# SCH_keyboard_2024-07-08.net
KiCad netlist of a schematic drawn in EasyEDA
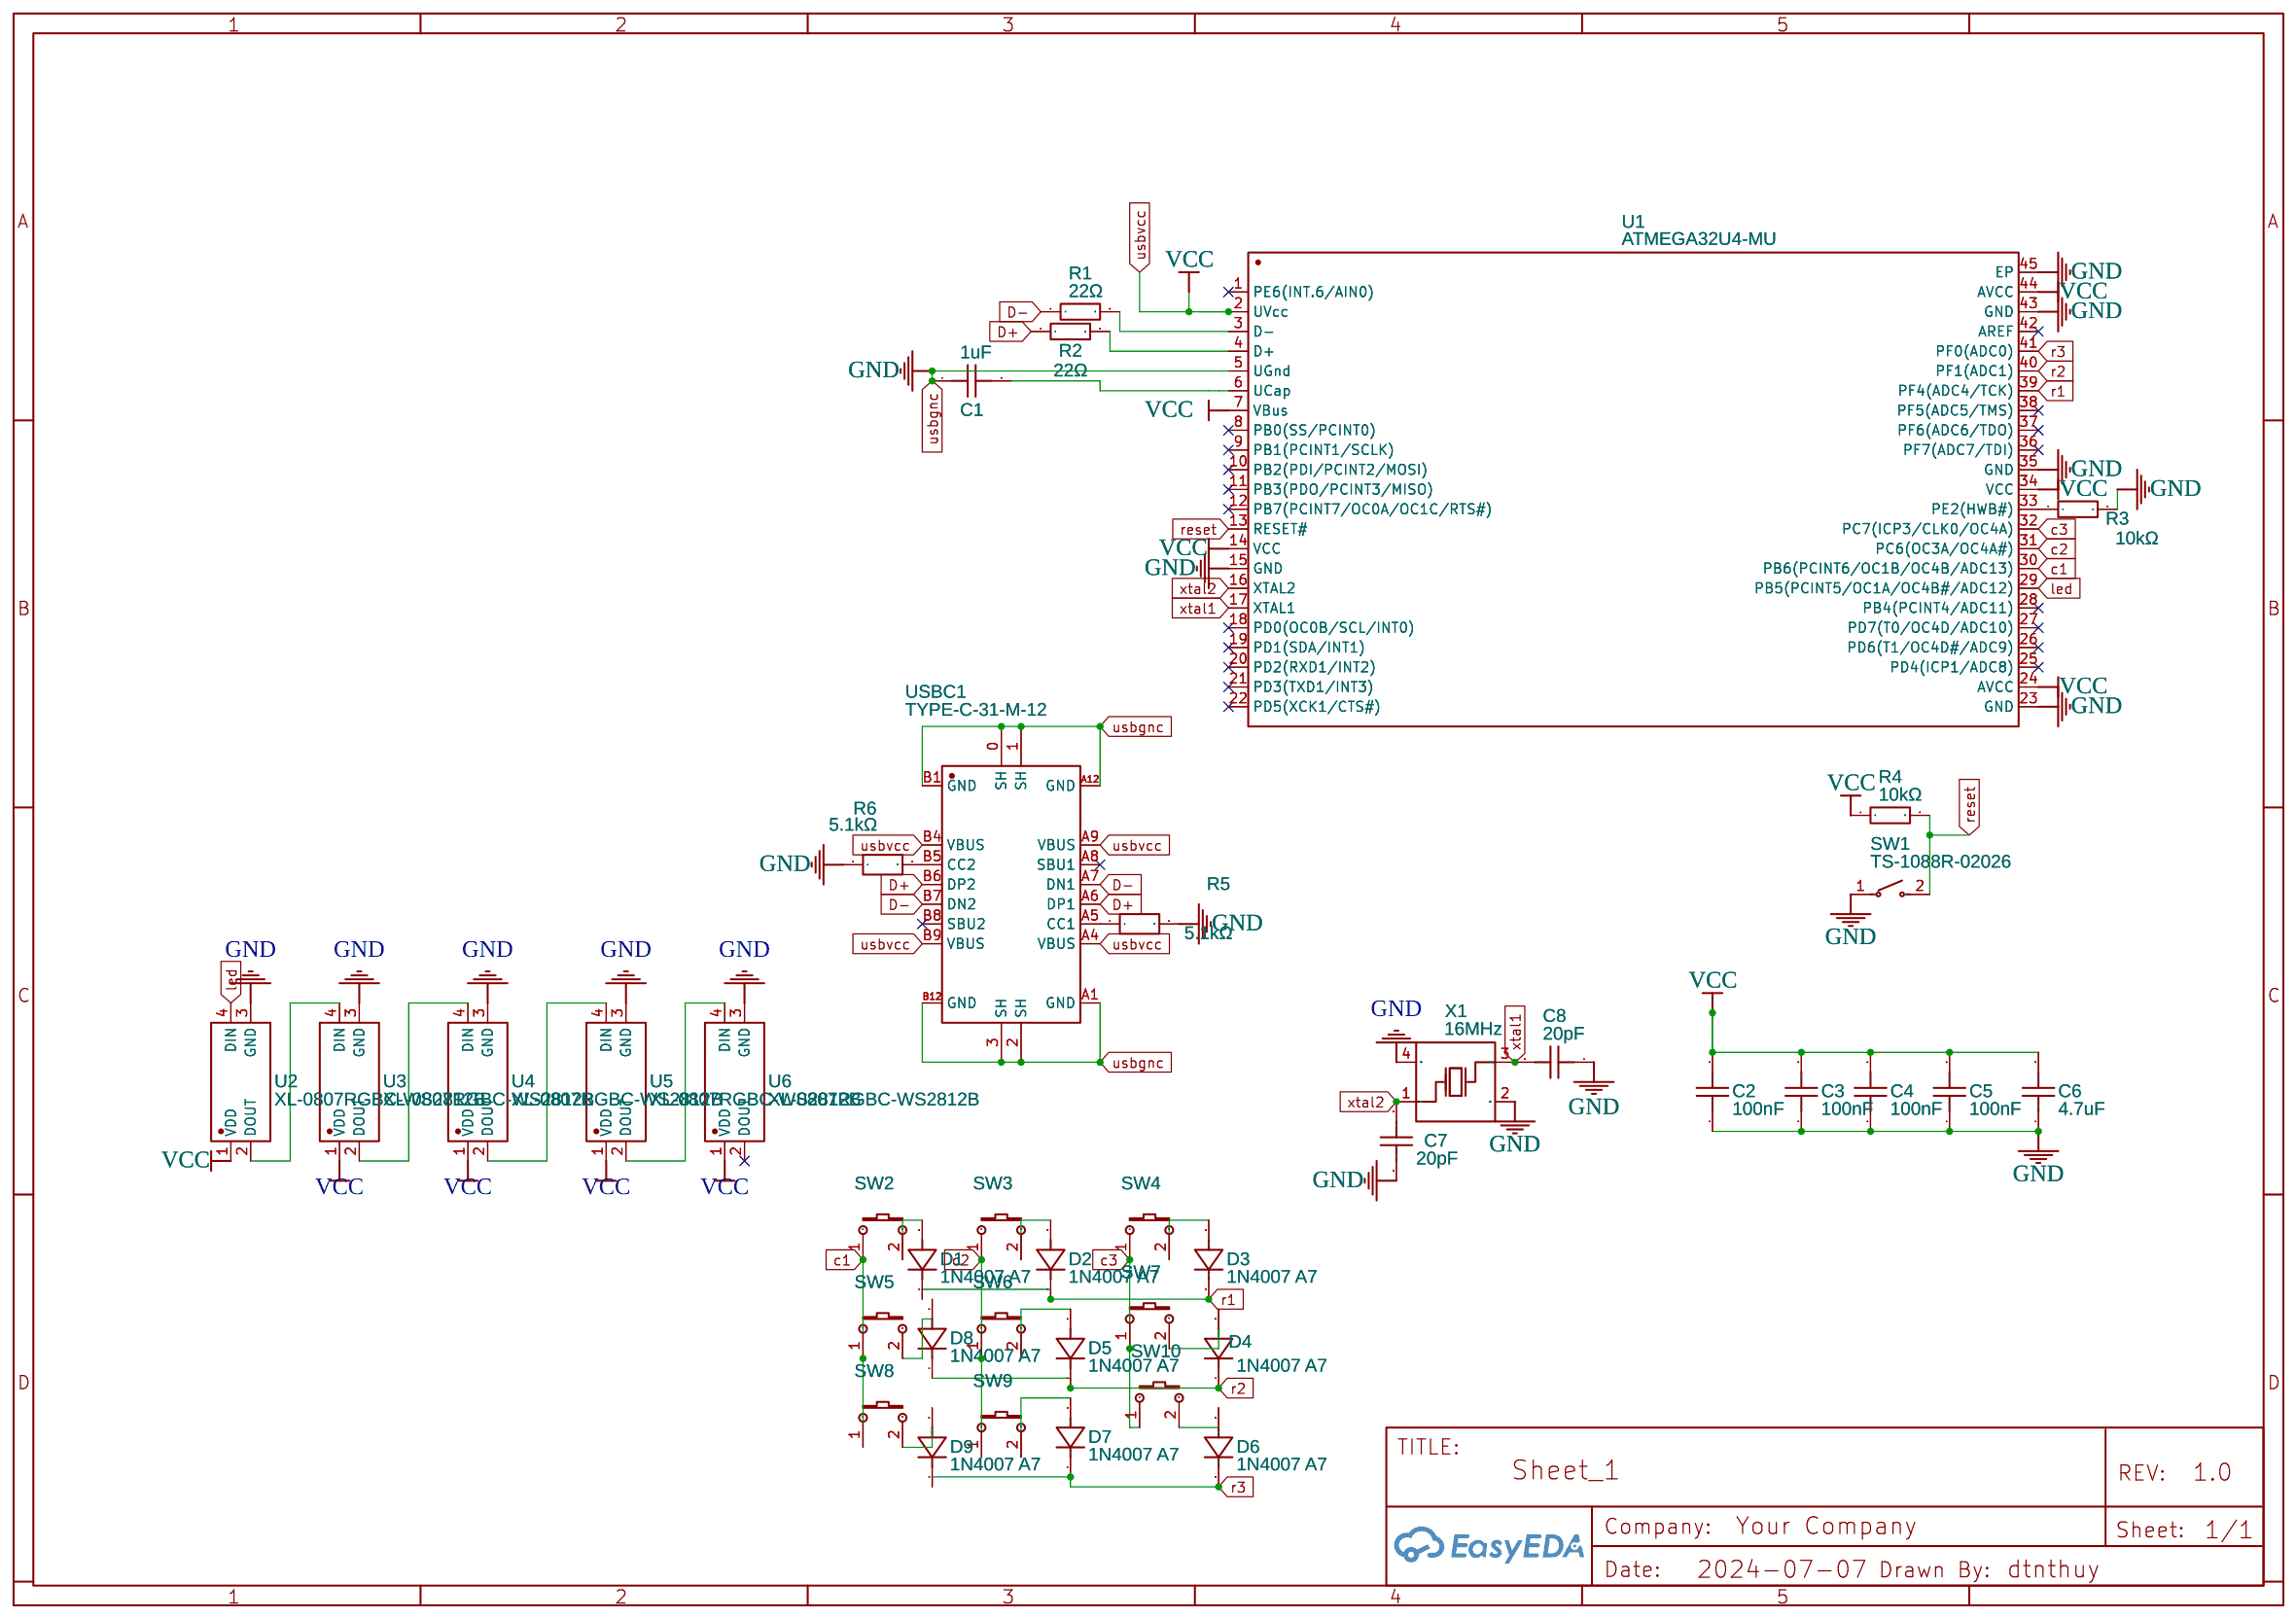
[diagram p0: schematic sheet]

(export (version "E")
  (design (tool "Eeschema 10.0.6"))
  (components
    (comp (ref "C1")
      (value "1uF")
      (fields
        (field (name "Manufacturer Part") "CS1608X7R105K250NRB")
        (field (name "Manufacturer") "SAMWHA(三和)")
      )
      (libsource (lib "") (part "CS1608X7R105K250NRB"))
    )
    (comp (ref "C2")
      (value "100nF")
      (fields
        (field (name "Manufacturer Part") "C0402X7R104K250NT")
        (field (name "Manufacturer") "SANYEAR(叁叶源)")
      )
      (libsource (lib "") (part "C0402X7R104K250NT"))
    )
    (comp (ref "C3")
      (value "100nF")
      (fields
        (field (name "Manufacturer Part") "C0402X7R104K250NT")
        (field (name "Manufacturer") "SANYEAR(叁叶源)")
      )
      (libsource (lib "") (part "C0402X7R104K250NT"))
    )
    (comp (ref "C4")
      (value "100nF")
      (fields
        (field (name "Manufacturer Part") "C0402X7R104K250NT")
        (field (name "Manufacturer") "SANYEAR(叁叶源)")
      )
      (libsource (lib "") (part "C0402X7R104K250NT"))
    )
    (comp (ref "C5")
      (value "100nF")
      (fields
        (field (name "Manufacturer Part") "C0402X7R104K250NT")
        (field (name "Manufacturer") "SANYEAR(叁叶源)")
      )
      (libsource (lib "") (part "C0402X7R104K250NT"))
    )
    (comp (ref "C6")
      (value "4.7uF")
      (fields (field (name "Manufacturer Part") "C1005X6S0G475MTJ00E") (field (name "Manufacturer") "TDK"))
      (libsource (lib "") (part "C1005X6S0G475MTJ00E"))
    )
    (comp (ref "C7")
      (value "20pF")
      (fields (field (name "Manufacturer Part") "0201CG200K500NT") (field (name "Manufacturer") "FH(风华)"))
      (libsource (lib "") (part "0201CG200K500NT"))
    )
    (comp (ref "C8")
      (value "20pF")
      (fields (field (name "Manufacturer Part") "0201CG200K500NT") (field (name "Manufacturer") "FH(风华)"))
      (libsource (lib "") (part "0201CG200K500NT_1"))
    )
    (comp (ref "D1")
      (value "1N4007 A7")
      (fields (field (name "Manufacturer") "MSKSEMI(美森科)"))
      (libsource (lib "") (part "1N4007 A7"))
    )
    (comp (ref "D2")
      (value "1N4007 A7")
      (fields (field (name "Manufacturer") "MSKSEMI(美森科)"))
      (libsource (lib "") (part "1N4007 A7"))
    )
    (comp (ref "D3")
      (value "1N4007 A7")
      (fields (field (name "Manufacturer") "MSKSEMI(美森科)"))
      (libsource (lib "") (part "1N4007 A7"))
    )
    (comp (ref "D4")
      (value "1N4007 A7")
      (fields (field (name "Manufacturer") "MSKSEMI(美森科)"))
      (libsource (lib "") (part "1N4007 A7"))
    )
    (comp (ref "D5")
      (value "1N4007 A7")
      (fields (field (name "Manufacturer") "MSKSEMI(美森科)"))
      (libsource (lib "") (part "1N4007 A7"))
    )
    (comp (ref "D6")
      (value "1N4007 A7")
      (fields (field (name "Manufacturer") "MSKSEMI(美森科)"))
      (libsource (lib "") (part "1N4007 A7"))
    )
    (comp (ref "D7")
      (value "1N4007 A7")
      (fields (field (name "Manufacturer") "MSKSEMI(美森科)"))
      (libsource (lib "") (part "1N4007 A7"))
    )
    (comp (ref "D8")
      (value "1N4007 A7")
      (fields (field (name "Manufacturer") "MSKSEMI(美森科)"))
      (libsource (lib "") (part "1N4007 A7"))
    )
    (comp (ref "D9")
      (value "1N4007 A7")
      (fields (field (name "Manufacturer") "MSKSEMI(美森科)"))
      (libsource (lib "") (part "1N4007 A7"))
    )
    (comp (ref "R1")
      (value "22Ω")
      (fields
        (field (name "Manufacturer Part") "0603WAJ0220T5E")
        (field (name "Manufacturer") "UNI-ROYAL(厚声)")
      )
      (libsource (lib "") (part "0603WAJ0220T5E"))
    )
    (comp (ref "R2")
      (value "22Ω")
      (fields
        (field (name "Manufacturer Part") "0603WAJ0220T5E")
        (field (name "Manufacturer") "UNI-ROYAL(厚声)")
      )
      (libsource (lib "") (part "0603WAJ0220T5E"))
    )
    (comp (ref "R3")
      (value "10kΩ")
      (fields
        (field (name "Manufacturer Part") "0805W8F1002T5E")
        (field (name "Manufacturer") "UNI-ROYAL(厚声)")
      )
      (libsource (lib "") (part "0805W8F1002T5E"))
    )
    (comp (ref "R4")
      (value "10kΩ")
      (fields
        (field (name "Manufacturer Part") "0805W8F1002T5E")
        (field (name "Manufacturer") "UNI-ROYAL(厚声)")
      )
      (libsource (lib "") (part "0805W8F1002T5E"))
    )
    (comp (ref "R5")
      (value "5.1kΩ")
      (fields (field (name "Manufacturer Part") "RK73H1JTTD5101D") (field (name "Manufacturer") "KOA"))
      (libsource (lib "") (part "RK73H1JTTD5101D"))
    )
    (comp (ref "R6")
      (value "5.1kΩ")
      (fields (field (name "Manufacturer Part") "RK73H1JTTD5101D") (field (name "Manufacturer") "KOA"))
      (libsource (lib "") (part "RK73H1JTTD5101D"))
    )
    (comp (ref "SW1")
      (value "TS-1088R-02026")
      (fields (field (name "Manufacturer") "XUNPU(讯普)"))
      (libsource (lib "") (part "TS-1088R-02026"))
    )
    (comp (ref "SW2")
      (value "MX1A-11NW")
      (fields (field (name "Manufacturer") "CHERRY"))
      (libsource (lib "") (part "MX1A-11NW"))
    )
    (comp (ref "SW3")
      (value "MX1A-11NW")
      (fields (field (name "Manufacturer") "CHERRY"))
      (libsource (lib "") (part "MX1A-11NW"))
    )
    (comp (ref "SW4")
      (value "MX1A-11NW")
      (fields (field (name "Manufacturer") "CHERRY"))
      (libsource (lib "") (part "MX1A-11NW"))
    )
    (comp (ref "SW5")
      (value "MX1A-11NW")
      (fields (field (name "Manufacturer") "CHERRY"))
      (libsource (lib "") (part "MX1A-11NW"))
    )
    (comp (ref "SW6")
      (value "MX1A-11NW")
      (fields (field (name "Manufacturer") "CHERRY"))
      (libsource (lib "") (part "MX1A-11NW"))
    )
    (comp (ref "SW7")
      (value "MX1A-11NW")
      (fields (field (name "Manufacturer") "CHERRY"))
      (libsource (lib "") (part "MX1A-11NW"))
    )
    (comp (ref "SW8")
      (value "MX1A-11NW")
      (fields (field (name "Manufacturer") "CHERRY"))
      (libsource (lib "") (part "MX1A-11NW"))
    )
    (comp (ref "SW9")
      (value "MX1A-11NW")
      (fields (field (name "Manufacturer") "CHERRY"))
      (libsource (lib "") (part "MX1A-11NW"))
    )
    (comp (ref "SW10")
      (value "MX1A-11NW")
      (fields (field (name "Manufacturer") "CHERRY"))
      (libsource (lib "") (part "MX1A-11NW"))
    )
    (comp (ref "U1")
      (value "ATMEGA32U4-MU")
      (fields (field (name "Manufacturer") "MICROCHIP(美国微芯)"))
      (libsource (lib "") (part "ATMEGA32U4-MU"))
    )
    (comp (ref "U2")
      (value "XL-0807RGBC-WS2812B")
      (fields (field (name "Manufacturer") "XINGLIGHT(成兴光)"))
      (libsource (lib "") (part "XL-0807RGBC-WS2812B"))
    )
    (comp (ref "U3")
      (value "XL-0807RGBC-WS2812B")
      (fields (field (name "Manufacturer") "XINGLIGHT(成兴光)"))
      (libsource (lib "") (part "XL-0807RGBC-WS2812B"))
    )
    (comp (ref "U4")
      (value "XL-0807RGBC-WS2812B")
      (fields (field (name "Manufacturer") "XINGLIGHT(成兴光)"))
      (libsource (lib "") (part "XL-0807RGBC-WS2812B"))
    )
    (comp (ref "U5")
      (value "XL-0807RGBC-WS2812B")
      (fields (field (name "Manufacturer") "XINGLIGHT(成兴光)"))
      (libsource (lib "") (part "XL-0807RGBC-WS2812B"))
    )
    (comp (ref "U6")
      (value "XL-0807RGBC-WS2812B")
      (fields (field (name "Manufacturer") "XINGLIGHT(成兴光)"))
      (libsource (lib "") (part "XL-0807RGBC-WS2812B"))
    )
    (comp (ref "USBC1")
      (value "TYPE-C-31-M-12")
      (fields (field (name "Manufacturer") "韩国韩荣"))
      (libsource (lib "") (part "TYPE-C-31-M-12"))
    )
    (comp (ref "X1")
      (value "16MHz")
      (fields (field (name "Manufacturer Part") "X322516MOB4SI") (field (name "Manufacturer") "YXC(扬兴晶振)"))
      (libsource (lib "") (part "X322516MOB4SI"))
    )
  )
  (nets
    (net (code "1") (name "D+") (class "Default")
      (node (ref "R2") (pin "1") (pinfunction "1_1") (pintype "input"))
      (node (ref "USBC1") (pin "A6") (pinfunction "DP1_A6") (pintype "unspecified"))
      (node (ref "USBC1") (pin "B6") (pinfunction "DP2_B6") (pintype "unspecified"))
    )
    (net (code "2") (name "D-") (class "Default")
      (node (ref "R1") (pin "1") (pinfunction "1_1") (pintype "input"))
      (node (ref "USBC1") (pin "A7") (pinfunction "DN1_A7") (pintype "unspecified"))
      (node (ref "USBC1") (pin "B7") (pinfunction "DN2_B7") (pintype "unspecified"))
    )
    (net (code "3") (name "Net-(D1-A)") (class "Default")
      (node (ref "D1") (pin "2") (pinfunction "A_2") (pintype "unspecified"))
      (node (ref "SW2") (pin "2") (pinfunction "2_2") (pintype "unspecified"))
    )
    (net (code "4") (name "Net-(D2-A)") (class "Default")
      (node (ref "D2") (pin "2") (pinfunction "A_2") (pintype "unspecified"))
      (node (ref "SW3") (pin "2") (pinfunction "2_2") (pintype "unspecified"))
    )
    (net (code "5") (name "Net-(D3-A)") (class "Default")
      (node (ref "D3") (pin "2") (pinfunction "A_2") (pintype "unspecified"))
      (node (ref "SW4") (pin "2") (pinfunction "2_2") (pintype "unspecified"))
    )
    (net (code "6") (name "Net-(D4-A)") (class "Default")
      (node (ref "D4") (pin "2") (pinfunction "A_2") (pintype "unspecified"))
      (node (ref "SW7") (pin "2") (pinfunction "2_2") (pintype "unspecified"))
    )
    (net (code "7") (name "Net-(D5-A)") (class "Default")
      (node (ref "D5") (pin "2") (pinfunction "A_2") (pintype "unspecified"))
      (node (ref "SW6") (pin "2") (pinfunction "2_2") (pintype "unspecified"))
    )
    (net (code "8") (name "Net-(D6-A)") (class "Default")
      (node (ref "D6") (pin "2") (pinfunction "A_2") (pintype "unspecified"))
      (node (ref "SW10") (pin "2") (pinfunction "2_2") (pintype "unspecified"))
    )
    (net (code "9") (name "Net-(D7-A)") (class "Default")
      (node (ref "D7") (pin "2") (pinfunction "A_2") (pintype "unspecified"))
      (node (ref "SW9") (pin "2") (pinfunction "2_2") (pintype "unspecified"))
    )
    (net (code "10") (name "Net-(D8-A)") (class "Default")
      (node (ref "D8") (pin "2") (pinfunction "A_2") (pintype "unspecified"))
      (node (ref "SW5") (pin "2") (pinfunction "2_2") (pintype "unspecified"))
    )
    (net (code "11") (name "Net-(D9-A)") (class "Default")
      (node (ref "D9") (pin "2") (pinfunction "A_2") (pintype "unspecified"))
      (node (ref "SW8") (pin "2") (pinfunction "2_2") (pintype "unspecified"))
    )
    (net (code "12") (name "Net-(U1-D+)") (class "Default")
      (node (ref "R2") (pin "2") (pinfunction "2_2") (pintype "input"))
      (node (ref "U1") (pin "4") (pinfunction "D+_4") (pintype "unspecified"))
    )
    (net (code "13") (name "Net-(U1-D-)") (class "Default")
      (node (ref "R1") (pin "2") (pinfunction "2_2") (pintype "input"))
      (node (ref "U1") (pin "3") (pinfunction "D-_3") (pintype "unspecified"))
    )
    (net (code "14") (name "Net-(U1-PE2(HWB#))") (class "Default")
      (node (ref "R3") (pin "1") (pinfunction "1_1") (pintype "input"))
      (node (ref "U1") (pin "33") (pinfunction "PE2(HWB#)_33") (pintype "unspecified"))
    )
    (net (code "15") (name "Net-(U1-UCap)") (class "Default")
      (node (ref "C1") (pin "2") (pinfunction "2_2") (pintype "unspecified"))
      (node (ref "U1") (pin "6") (pinfunction "UCap_6") (pintype "unspecified"))
    )
    (net (code "16") (name "Net-(U2-DOUT)") (class "Default")
      (node (ref "U2") (pin "2") (pinfunction "DOUT_2") (pintype "unspecified"))
      (node (ref "U3") (pin "4") (pinfunction "DIN_4") (pintype "unspecified"))
    )
    (net (code "17") (name "Net-(U3-DOUT)") (class "Default")
      (node (ref "U3") (pin "2") (pinfunction "DOUT_2") (pintype "unspecified"))
      (node (ref "U4") (pin "4") (pinfunction "DIN_4") (pintype "unspecified"))
    )
    (net (code "18") (name "Net-(U4-DOUT)") (class "Default")
      (node (ref "U4") (pin "2") (pinfunction "DOUT_2") (pintype "unspecified"))
      (node (ref "U5") (pin "4") (pinfunction "DIN_4") (pintype "unspecified"))
    )
    (net (code "19") (name "Net-(U5-DOUT)") (class "Default")
      (node (ref "U5") (pin "2") (pinfunction "DOUT_2") (pintype "unspecified"))
      (node (ref "U6") (pin "4") (pinfunction "DIN_4") (pintype "unspecified"))
    )
    (net (code "20") (name "Net-(USBC1-CC1)") (class "Default")
      (node (ref "R5") (pin "1") (pinfunction "1_1") (pintype "unspecified"))
      (node (ref "USBC1") (pin "A5") (pinfunction "CC1_A5") (pintype "unspecified"))
    )
    (net (code "21") (name "Net-(USBC1-CC2)") (class "Default")
      (node (ref "R6") (pin "2") (pinfunction "2_2") (pintype "unspecified"))
      (node (ref "USBC1") (pin "B5") (pinfunction "CC2_B5") (pintype "unspecified"))
    )
    (net (code "22") (name "c1") (class "Default")
      (node (ref "SW2") (pin "1") (pinfunction "1_1") (pintype "unspecified"))
      (node (ref "SW5") (pin "1") (pinfunction "1_1") (pintype "unspecified"))
      (node (ref "SW8") (pin "1") (pinfunction "1_1") (pintype "unspecified"))
      (node (ref "U1") (pin "30") (pinfunction "PB6(PCINT6/OC1B/OC4B/ADC13)_30") (pintype "unspecified"))
    )
    (net (code "23") (name "c2") (class "Default")
      (node (ref "SW3") (pin "1") (pinfunction "1_1") (pintype "unspecified"))
      (node (ref "SW6") (pin "1") (pinfunction "1_1") (pintype "unspecified"))
      (node (ref "SW9") (pin "1") (pinfunction "1_1") (pintype "unspecified"))
      (node (ref "U1") (pin "31") (pinfunction "PC6(OC3A/OC4A#)_31") (pintype "unspecified"))
    )
    (net (code "24") (name "c3") (class "Default")
      (node (ref "SW10") (pin "1") (pinfunction "1_1") (pintype "unspecified"))
      (node (ref "SW4") (pin "1") (pinfunction "1_1") (pintype "unspecified"))
      (node (ref "SW7") (pin "1") (pinfunction "1_1") (pintype "unspecified"))
      (node (ref "U1") (pin "32") (pinfunction "PC7(ICP3/CLK0/OC4A)_32") (pintype "unspecified"))
    )
    (net (code "25") (name "led") (class "Default")
      (node (ref "U1") (pin "29") (pinfunction "PB5(PCINT5/OC1A/OC4B#/ADC12)_29") (pintype "unspecified"))
      (node (ref "U2") (pin "4") (pinfunction "DIN_4") (pintype "unspecified"))
    )
    (net (code "26") (name "r1") (class "Default")
      (node (ref "D1") (pin "1") (pinfunction "K_1") (pintype "unspecified"))
      (node (ref "D2") (pin "1") (pinfunction "K_1") (pintype "unspecified"))
      (node (ref "D3") (pin "1") (pinfunction "K_1") (pintype "unspecified"))
      (node (ref "U1") (pin "39") (pinfunction "PF4(ADC4/TCK)_39") (pintype "unspecified"))
    )
    (net (code "27") (name "r2") (class "Default")
      (node (ref "D4") (pin "1") (pinfunction "K_1") (pintype "unspecified"))
      (node (ref "D5") (pin "1") (pinfunction "K_1") (pintype "unspecified"))
      (node (ref "D8") (pin "1") (pinfunction "K_1") (pintype "unspecified"))
      (node (ref "U1") (pin "40") (pinfunction "PF1(ADC1)_40") (pintype "unspecified"))
    )
    (net (code "28") (name "r3") (class "Default")
      (node (ref "D6") (pin "1") (pinfunction "K_1") (pintype "unspecified"))
      (node (ref "D7") (pin "1") (pinfunction "K_1") (pintype "unspecified"))
      (node (ref "D9") (pin "1") (pinfunction "K_1") (pintype "unspecified"))
      (node (ref "U1") (pin "41") (pinfunction "PF0(ADC0)_41") (pintype "unspecified"))
    )
    (net (code "29") (name "reset") (class "Default")
      (node (ref "R4") (pin "2") (pinfunction "2_2") (pintype "input"))
      (node (ref "SW1") (pin "2") (pinfunction "2_2") (pintype "unspecified"))
      (node (ref "U1") (pin "13") (pinfunction "RESET#_13") (pintype "unspecified"))
    )
    (net (code "30") (name "unconnected-(U1-AREF-Pad42)") (class "Default")
      (node (ref "U1") (pin "42") (pinfunction "AREF_42") (pintype "unspecified+no_connect"))
    )
    (net (code "31") (name "unconnected-(U1-PB0(SS{slash}PCINT0)-Pad8)") (class "Default")
      (node (ref "U1") (pin "8") (pinfunction "PB0(SS/PCINT0)_8") (pintype "unspecified+no_connect"))
    )
    (net (code "32") (name "unconnected-(U1-PB1(PCINT1{slash}SCLK)-Pad9)") (class "Default")
      (node (ref "U1") (pin "9") (pinfunction "PB1(PCINT1/SCLK)_9") (pintype "unspecified+no_connect"))
    )
    (net (code "33") (name "unconnected-(U1-PB2(PDI{slash}PCINT2{slash}MOSI)-Pad10)") (class "Default")
      (node (ref "U1") (pin "10") (pinfunction "PB2(PDI/PCINT2/MOSI)_10") (pintype "unspecified+no_connect"))
    )
    (net (code "34") (name "unconnected-(U1-PB3(PDO{slash}PCINT3{slash}MISO)-Pad11)") (class "Default")
      (node (ref "U1") (pin "11") (pinfunction "PB3(PDO/PCINT3/MISO)_11") (pintype "unspecified+no_connect"))
    )
    (net (code "35") (name "unconnected-(U1-PB4(PCINT4{slash}ADC11)-Pad28)") (class "Default")
      (node (ref "U1") (pin "28") (pinfunction "PB4(PCINT4/ADC11)_28") (pintype "unspecified+no_connect"))
    )
    (net (code "36") (name "unconnected-(U1-PB7(PCINT7{slash}OC0A{slash}OC1C{slash}RTS#)-Pad12)") (class "Default")
      (node (ref "U1") (pin "12") (pinfunction "PB7(PCINT7/OC0A/OC1C/RTS#)_12") (pintype "unspecified+no_connect"))
    )
    (net (code "37") (name "unconnected-(U1-PD0(OC0B{slash}SCL{slash}INT0)-Pad18)") (class "Default")
      (node (ref "U1") (pin "18") (pinfunction "PD0(OC0B/SCL/INT0)_18") (pintype "unspecified+no_connect"))
    )
    (net (code "38") (name "unconnected-(U1-PD1(SDA{slash}INT1)-Pad19)") (class "Default")
      (node (ref "U1") (pin "19") (pinfunction "PD1(SDA/INT1)_19") (pintype "unspecified+no_connect"))
    )
    (net (code "39") (name "unconnected-(U1-PD2(RXD1{slash}INT2)-Pad20)") (class "Default")
      (node (ref "U1") (pin "20") (pinfunction "PD2(RXD1/INT2)_20") (pintype "unspecified+no_connect"))
    )
    (net (code "40") (name "unconnected-(U1-PD3(TXD1{slash}INT3)-Pad21)") (class "Default")
      (node (ref "U1") (pin "21") (pinfunction "PD3(TXD1/INT3)_21") (pintype "unspecified+no_connect"))
    )
    (net (code "41") (name "unconnected-(U1-PD4(ICP1{slash}ADC8)-Pad25)") (class "Default")
      (node (ref "U1") (pin "25") (pinfunction "PD4(ICP1/ADC8)_25") (pintype "unspecified+no_connect"))
    )
    (net (code "42") (name "unconnected-(U1-PD5(XCK1{slash}CTS#)-Pad22)") (class "Default")
      (node (ref "U1") (pin "22") (pinfunction "PD5(XCK1/CTS#)_22") (pintype "unspecified+no_connect"))
    )
    (net (code "43") (name "unconnected-(U1-PD6(T1{slash}OC4D#{slash}ADC9)-Pad26)") (class "Default")
      (node (ref "U1") (pin "26") (pinfunction "PD6(T1/OC4D#/ADC9)_26") (pintype "unspecified+no_connect"))
    )
    (net (code "44") (name "unconnected-(U1-PD7(T0{slash}OC4D{slash}ADC10)-Pad27)") (class "Default")
      (node (ref "U1") (pin "27") (pinfunction "PD7(T0/OC4D/ADC10)_27") (pintype "unspecified+no_connect"))
    )
    (net (code "45") (name "unconnected-(U1-PE6(INT.6{slash}AIN0)-Pad1)") (class "Default")
      (node (ref "U1") (pin "1") (pinfunction "PE6(INT.6/AIN0)_1") (pintype "unspecified+no_connect"))
    )
    (net (code "46") (name "unconnected-(U1-PF5(ADC5{slash}TMS)-Pad38)") (class "Default")
      (node (ref "U1") (pin "38") (pinfunction "PF5(ADC5/TMS)_38") (pintype "unspecified+no_connect"))
    )
    (net (code "47") (name "unconnected-(U1-PF6(ADC6{slash}TDO)-Pad37)") (class "Default")
      (node (ref "U1") (pin "37") (pinfunction "PF6(ADC6/TDO)_37") (pintype "unspecified+no_connect"))
    )
    (net (code "48") (name "unconnected-(U1-PF7(ADC7{slash}TDI)-Pad36)") (class "Default")
      (node (ref "U1") (pin "36") (pinfunction "PF7(ADC7/TDI)_36") (pintype "unspecified+no_connect"))
    )
    (net (code "49") (name "unconnected-(U6-DOUT-Pad2)") (class "Default")
      (node (ref "U6") (pin "2") (pinfunction "DOUT_2") (pintype "unspecified+no_connect"))
    )
    (net (code "50") (name "unconnected-(USBC1-SBU1-PadA8)") (class "Default")
      (node (ref "USBC1") (pin "A8") (pinfunction "SBU1_A8") (pintype "unspecified+no_connect"))
    )
    (net (code "51") (name "unconnected-(USBC1-SBU2-PadB8)") (class "Default")
      (node (ref "USBC1") (pin "B8") (pinfunction "SBU2_B8") (pintype "unspecified+no_connect"))
    )
    (net (code "52") (name "usbgnc") (class "Default")
      (node (ref "C1") (pin "1") (pinfunction "1_1") (pintype "unspecified"))
      (node (ref "C2") (pin "1") (pinfunction "1_1") (pintype "unspecified"))
      (node (ref "C3") (pin "1") (pinfunction "1_1") (pintype "unspecified"))
      (node (ref "C4") (pin "1") (pinfunction "1_1") (pintype "unspecified"))
      (node (ref "C5") (pin "1") (pinfunction "1_1") (pintype "unspecified"))
      (node (ref "C6") (pin "1") (pinfunction "1_1") (pintype "unspecified"))
      (node (ref "C7") (pin "1") (pinfunction "1_1") (pintype "unspecified"))
      (node (ref "C8") (pin "1") (pinfunction "1_1") (pintype "unspecified"))
      (node (ref "R3") (pin "2") (pinfunction "2_2") (pintype "input"))
      (node (ref "R5") (pin "2") (pinfunction "2_2") (pintype "unspecified"))
      (node (ref "R6") (pin "1") (pinfunction "1_1") (pintype "unspecified"))
      (node (ref "SW1") (pin "1") (pinfunction "1_1") (pintype "unspecified"))
      (node (ref "U1") (pin "15") (pinfunction "GND_15") (pintype "unspecified"))
      (node (ref "U1") (pin "23") (pinfunction "GND_23") (pintype "unspecified"))
      (node (ref "U1") (pin "35") (pinfunction "GND_35") (pintype "unspecified"))
      (node (ref "U1") (pin "43") (pinfunction "GND_43") (pintype "unspecified"))
      (node (ref "U1") (pin "45") (pinfunction "EP_45") (pintype "unspecified"))
      (node (ref "U1") (pin "5") (pinfunction "UGnd_5") (pintype "unspecified"))
      (node (ref "U2") (pin "3") (pinfunction "GND_3") (pintype "unspecified"))
      (node (ref "U3") (pin "3") (pinfunction "GND_3") (pintype "unspecified"))
      (node (ref "U4") (pin "3") (pinfunction "GND_3") (pintype "unspecified"))
      (node (ref "U5") (pin "3") (pinfunction "GND_3") (pintype "unspecified"))
      (node (ref "U6") (pin "3") (pinfunction "GND_3") (pintype "unspecified"))
      (node (ref "USBC1") (pin "0") (pinfunction "SH_0") (pintype "unspecified"))
      (node (ref "USBC1") (pin "1") (pinfunction "SH_1") (pintype "unspecified"))
      (node (ref "USBC1") (pin "2") (pinfunction "SH_2") (pintype "unspecified"))
      (node (ref "USBC1") (pin "3") (pinfunction "SH_3") (pintype "unspecified"))
      (node (ref "USBC1") (pin "A1") (pinfunction "GND_A1") (pintype "unspecified"))
      (node (ref "USBC1") (pin "A12") (pinfunction "GND_A12") (pintype "unspecified"))
      (node (ref "USBC1") (pin "B1") (pinfunction "GND_B1") (pintype "unspecified"))
      (node (ref "USBC1") (pin "B12") (pinfunction "GND_B12") (pintype "unspecified"))
      (node (ref "X1") (pin "2") (pinfunction "GND_2") (pintype "unspecified"))
      (node (ref "X1") (pin "4") (pinfunction "GND_4") (pintype "unspecified"))
    )
    (net (code "53") (name "usbvcc") (class "Default")
      (node (ref "C2") (pin "2") (pinfunction "2_2") (pintype "unspecified"))
      (node (ref "C3") (pin "2") (pinfunction "2_2") (pintype "unspecified"))
      (node (ref "C4") (pin "2") (pinfunction "2_2") (pintype "unspecified"))
      (node (ref "C5") (pin "2") (pinfunction "2_2") (pintype "unspecified"))
      (node (ref "C6") (pin "2") (pinfunction "2_2") (pintype "unspecified"))
      (node (ref "R4") (pin "1") (pinfunction "1_1") (pintype "input"))
      (node (ref "U1") (pin "14") (pinfunction "VCC_14") (pintype "unspecified"))
      (node (ref "U1") (pin "2") (pinfunction "UVcc_2") (pintype "unspecified"))
      (node (ref "U1") (pin "24") (pinfunction "AVCC_24") (pintype "unspecified"))
      (node (ref "U1") (pin "34") (pinfunction "VCC_34") (pintype "unspecified"))
      (node (ref "U1") (pin "44") (pinfunction "AVCC_44") (pintype "unspecified"))
      (node (ref "U1") (pin "7") (pinfunction "VBus_7") (pintype "unspecified"))
      (node (ref "U2") (pin "1") (pinfunction "VDD_1") (pintype "unspecified"))
      (node (ref "U3") (pin "1") (pinfunction "VDD_1") (pintype "unspecified"))
      (node (ref "U4") (pin "1") (pinfunction "VDD_1") (pintype "unspecified"))
      (node (ref "U5") (pin "1") (pinfunction "VDD_1") (pintype "unspecified"))
      (node (ref "U6") (pin "1") (pinfunction "VDD_1") (pintype "unspecified"))
      (node (ref "USBC1") (pin "A4") (pinfunction "VBUS_A4") (pintype "unspecified"))
      (node (ref "USBC1") (pin "A9") (pinfunction "VBUS_A9") (pintype "unspecified"))
      (node (ref "USBC1") (pin "B4") (pinfunction "VBUS_B4") (pintype "unspecified"))
      (node (ref "USBC1") (pin "B9") (pinfunction "VBUS_B9") (pintype "unspecified"))
    )
    (net (code "54") (name "xtal1") (class "Default")
      (node (ref "C8") (pin "2") (pinfunction "2_2") (pintype "unspecified"))
      (node (ref "U1") (pin "17") (pinfunction "XTAL1_17") (pintype "unspecified"))
      (node (ref "X1") (pin "3") (pinfunction "OSC2_3") (pintype "unspecified"))
    )
    (net (code "55") (name "xtal2") (class "Default")
      (node (ref "C7") (pin "2") (pinfunction "2_2") (pintype "unspecified"))
      (node (ref "U1") (pin "16") (pinfunction "XTAL2_16") (pintype "unspecified"))
      (node (ref "X1") (pin "1") (pinfunction "OSC1_1") (pintype "unspecified"))
    )
  )
)
